# Sheet-BATTERY-V1_0.net
KiCad netlist of a schematic drawn in Altium Designer
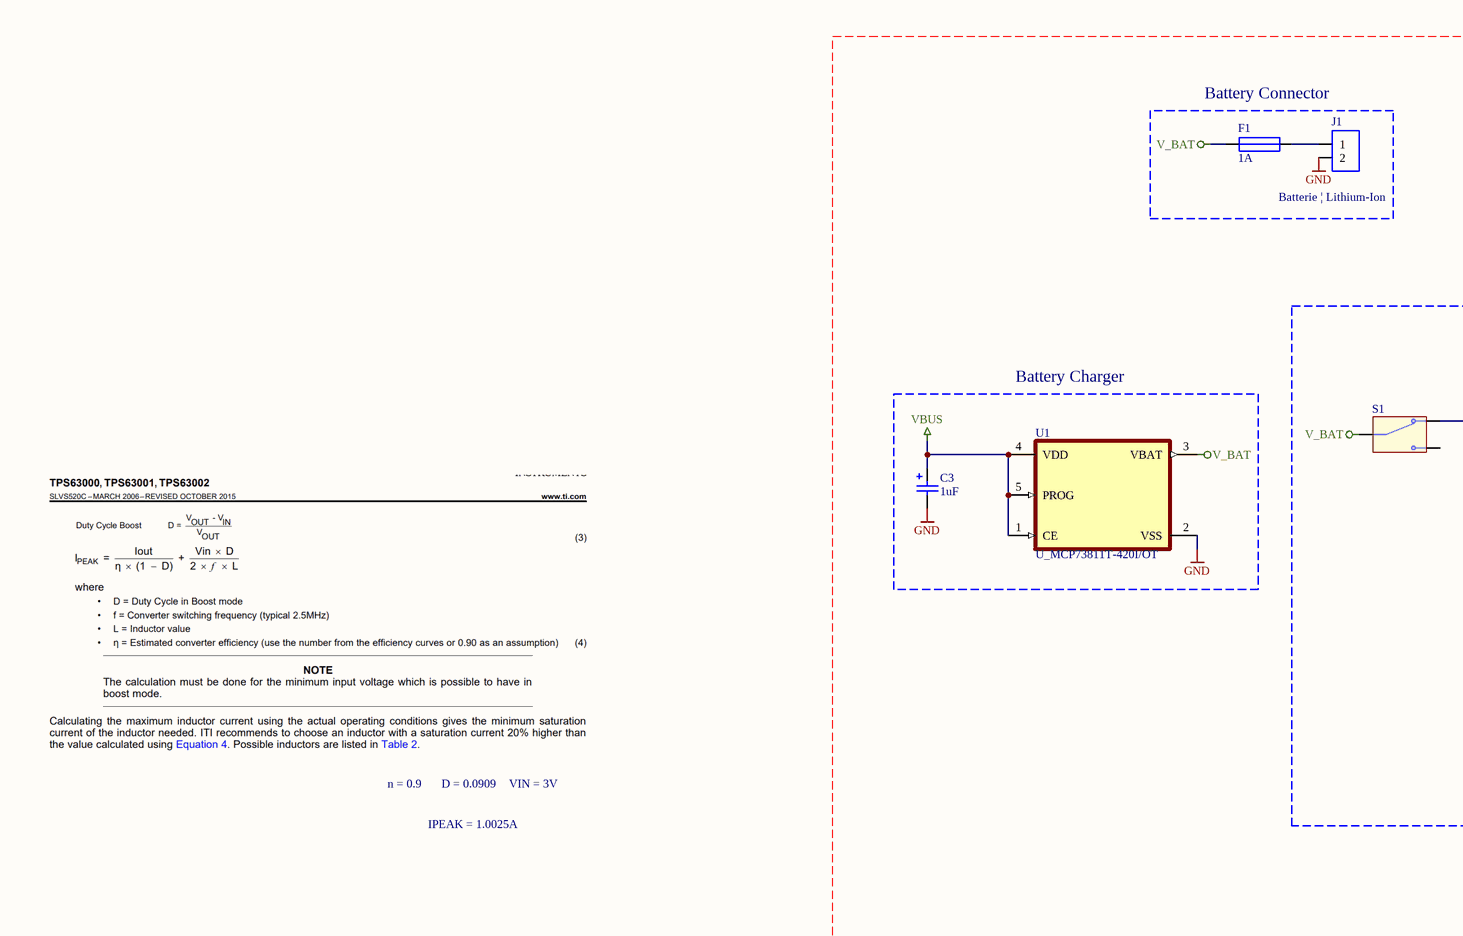
[diagram p0: Sheet-BATTERY-V1.0.SchDoc, left]
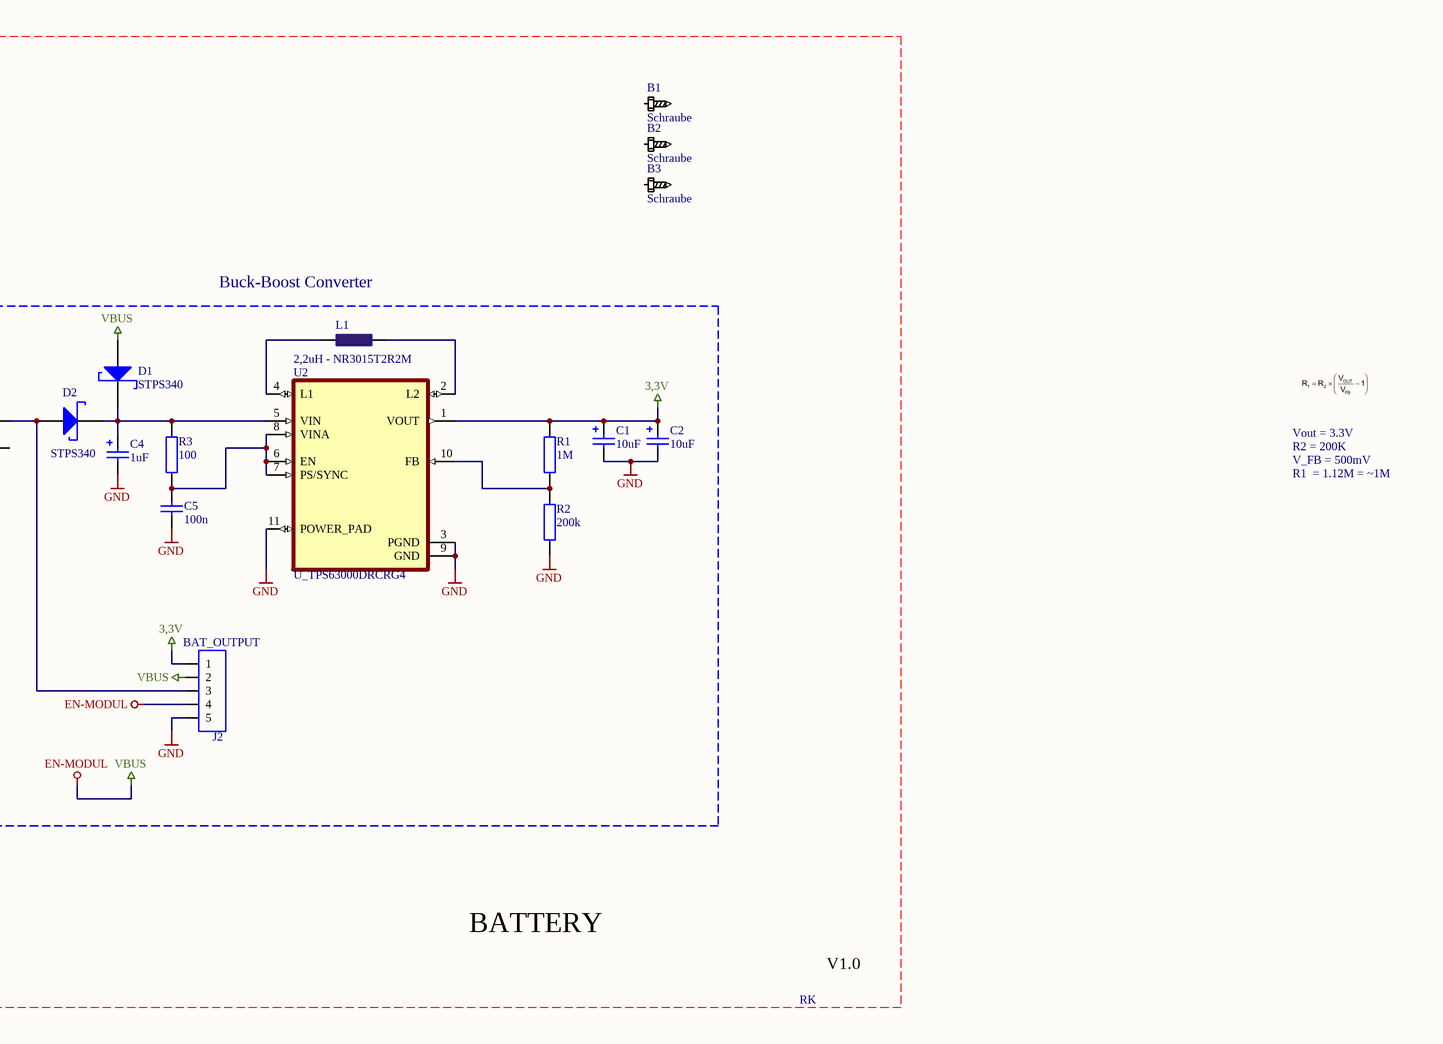
[diagram p1: Sheet-BATTERY-V1.0.SchDoc, right]

(export (version "E")
  (design (tool "Eeschema 10.0.6"))
  (components
    (comp (ref "B1")
      (value "Schraube")
      (footprint "B_Schraube-M3 PAD")
      (description "Schraubenloch für M3 Schrauben")
      (libsource (lib "SCHLIB-PCSB_5.1.3") (part "B_Schraube"))
    )
    (comp (ref "B2")
      (value "Schraube")
      (footprint "B_Schraube-M3 PAD")
      (description "Schraubenloch für M3 Schrauben")
      (libsource (lib "SCHLIB-PCSB_5.1.3") (part "B_Schraube"))
    )
    (comp (ref "B3")
      (value "Schraube")
      (footprint "B_Schraube-M3 PAD")
      (description "Schraubenloch für M3 Schrauben")
      (libsource (lib "SCHLIB-PCSB_5.1.3") (part "B_Schraube"))
    )
    (comp (ref "C1")
      (value "10uF")
      (footprint "C_SMD_B-Typ")
      (description "SMD Elektrolytkondensator")
      (libsource (lib "SCHLIB-PCSB_5.1.3") (part "C_SMD_ELK"))
    )
    (comp (ref "C2")
      (value "10uF")
      (footprint "C_SMD_B-Typ")
      (description "SMD Elektrolytkondensator")
      (libsource (lib "SCHLIB-PCSB_5.1.3") (part "C_SMD_ELK"))
    )
    (comp (ref "C3")
      (value "1uF")
      (footprint "C_SMD_B-Typ")
      (description "SMD Elektrolytkondensator")
      (libsource (lib "SCHLIB-PCSB_5.1.3") (part "C_SMD_ELK"))
    )
    (comp (ref "C4")
      (value "1uF")
      (footprint "C_SMD_B-Typ")
      (description "SMD Elektrolytkondensator")
      (libsource (lib "SCHLIB-PCSB_5.1.3") (part "C_SMD_ELK"))
    )
    (comp (ref "C5")
      (value "100n")
      (footprint "C_SMD_0603")
      (description "Kondensator SMD Universal, Keramik, Folie, usw.")
      (libsource (lib "SCHLIB-PCSB_5.1.3") (part "C_SMD_KO"))
    )
    (comp (ref "D1")
      (value "STPS340")
      (footprint "D_DO-214")
      (description "Diode SMD Schottky")
      (libsource (lib "SCHLIB-PCSB_5.1.3") (part "D_SMD_Schottky"))
    )
    (comp (ref "D2")
      (value "STPS340")
      (footprint "D_DO-214")
      (description "Diode SMD Schottky")
      (libsource (lib "SCHLIB-PCSB_5.1.3") (part "D_SMD_Schottky"))
    )
    (comp (ref "F1")
      (value "1A")
      (footprint "F_OMF63_Schurtner")
      (description "Sicherung")
      (libsource (lib "SCHLIB-PCSB_5.1.3") (part "F_THT_Fuse"))
    )
    (comp (ref "J1")
      (value "Batterie ¦ Lithium-Ion")
      (footprint "J_THT_Printklemme 2x")
      (description "Stecker")
      (libsource (lib "SCHLIB-PCSB_5.1.3") (part "J_THT_CON2"))
    )
    (comp (ref "J2")
      (value "BAT_OUTPUT")
      (footprint "SIP-5")
      (description "Stecker")
      (libsource (lib "SCHLIB-PCSB_5.1.3") (part "J_THT_CON5"))
    )
    (comp (ref "L1")
      (value "2,2uH - NR3015T2R2M")
      (footprint "L_SMD_ND_NR3015T2R2M")
      (description "Spule SMD")
      (libsource (lib "SCHLIB-PCSB_5.1.3") (part "L_SMD_Spule"))
    )
    (comp (ref "R1")
      (value "1M")
      (footprint "R_SMD_0805")
      (description "Widerstand SMD")
      (libsource (lib "SCHLIB-PCSB_5.1.3") (part "R_SMD_Widerstand"))
    )
    (comp (ref "R2")
      (value "200k")
      (footprint "R_SMD_0805")
      (description "Widerstand SMD")
      (libsource (lib "SCHLIB-PCSB_5.1.3") (part "R_SMD_Widerstand"))
    )
    (comp (ref "R3")
      (value "100")
      (footprint "R_SMD_0805")
      (description "Widerstand SMD")
      (libsource (lib "SCHLIB-PCSB_5.1.3") (part "R_SMD_Widerstand"))
    )
    (comp (ref "S1")
      (value "~")
      (footprint "S_THT_SW-3Pol")
      (description "Toggle Switch")
      (fields (field (name "MP") "100SP1T1B4M2QE"))
      (libsource (lib "SCHLIB-PCSB_5.1.3") (part "S_THT_Schalter 3-Pol."))
    )
    (comp (ref "U1")
      (value "U_MCP73811T-420I/OT")
      (footprint "SOT95P280X145-5N")
      (description "Charger IC Lithium Ion/Polymer SOT-23-5")
      (fields (field (name "MF") "Microchip") (field (name "MP") "MCP73811T-420I/OT"))
      (libsource (lib "SCHLIB-PCSB_5.1.3") (part "U_MCP73811T-420I/OT"))
    )
    (comp (ref "U2")
      (value "U_TPS63000DRCRG4")
      (footprint "VREG_V62/16624-01YE")
      (description "High efficiency Buck-Boost Converter with 1.8A Current Switches in 3x3 QFN 10-VSON -40 to 85")
      (fields (field (name "MF") "Texas Instruments") (field (name "MP") "TPS63000DRCRG4"))
      (libsource (lib "SCHLIB-PCSB_5.1.3") (part "U_TPS63000DRCRG4"))
    )
  )
  (nets
    (net (code "1") (name "3,3V") (class "Default")
      (node (ref "C1") (pin "1") (pinfunction "1_1") (pintype "passive"))
      (node (ref "C2") (pin "1") (pinfunction "1_1") (pintype "passive"))
      (node (ref "J2") (pin "1") (pinfunction "1_1") (pintype "passive"))
      (node (ref "R1") (pin "2") (pintype "passive"))
      (node (ref "U2") (pin "1") (pinfunction "VOUT_1") (pintype "output"))
    )
    (net (code "2") (name "EN-MODUL") (class "Default")
      (node (ref "C3") (pin "1") (pinfunction "1_1") (pintype "passive"))
      (node (ref "D1") (pin "1") (pinfunction "A_1") (pintype "passive"))
      (node (ref "J2") (pin "2") (pinfunction "2_2") (pintype "passive"))
      (node (ref "J2") (pin "4") (pinfunction "4_4") (pintype "passive"))
      (node (ref "U1") (pin "1") (pinfunction "CE_1") (pintype "input"))
      (node (ref "U1") (pin "4") (pinfunction "VDD_4") (pintype "power_in"))
      (node (ref "U1") (pin "5") (pinfunction "PROG_5") (pintype "input"))
    )
    (net (code "3") (name "GND") (class "Default")
      (node (ref "C1") (pin "2") (pinfunction "2_2") (pintype "passive"))
      (node (ref "C2") (pin "2") (pinfunction "2_2") (pintype "passive"))
      (node (ref "C3") (pin "2") (pinfunction "2_2") (pintype "passive"))
      (node (ref "C4") (pin "2") (pinfunction "2_2") (pintype "passive"))
      (node (ref "C5") (pin "2") (pintype "passive"))
      (node (ref "J1") (pin "2") (pinfunction "2_2") (pintype "passive"))
      (node (ref "J2") (pin "5") (pinfunction "5_5") (pintype "passive"))
      (node (ref "R2") (pin "1") (pintype "passive"))
      (node (ref "U1") (pin "2") (pinfunction "VSS_2") (pintype "power_in"))
      (node (ref "U2") (pin "11") (pinfunction "POWER_PAD_11") (pintype "bidirectional"))
      (node (ref "U2") (pin "3") (pinfunction "PGND_3") (pintype "power_in"))
      (node (ref "U2") (pin "9") (pinfunction "GND_9") (pintype "power_in"))
    )
    (net (code "4") (name "Net-(D1-K)") (class "Default")
      (node (ref "C4") (pin "1") (pinfunction "1_1") (pintype "passive"))
      (node (ref "D1") (pin "2") (pinfunction "K_2") (pintype "passive"))
      (node (ref "D2") (pin "2") (pinfunction "K_2") (pintype "passive"))
      (node (ref "R3") (pin "2") (pintype "passive"))
      (node (ref "U2") (pin "5") (pinfunction "VIN_5") (pintype "input"))
    )
    (net (code "5") (name "Net-(D2-A)") (class "Default")
      (node (ref "D2") (pin "1") (pinfunction "A_1") (pintype "passive"))
      (node (ref "J2") (pin "3") (pinfunction "3_3") (pintype "passive"))
      (node (ref "S1") (pin "1") (pinfunction "1_1") (pintype "passive"))
    )
    (net (code "6") (name "Net-(F1-Pad2)") (class "Default")
      (node (ref "F1") (pin "2") (pinfunction "2_2") (pintype "passive"))
      (node (ref "J1") (pin "1") (pinfunction "1_1") (pintype "passive"))
    )
    (net (code "7") (name "Net-(U2-EN)") (class "Default")
      (node (ref "C5") (pin "1") (pintype "passive"))
      (node (ref "R3") (pin "1") (pintype "passive"))
      (node (ref "U2") (pin "6") (pinfunction "EN_6") (pintype "input"))
      (node (ref "U2") (pin "7") (pinfunction "PS/SYNC_7") (pintype "input"))
      (node (ref "U2") (pin "8") (pinfunction "VINA_8") (pintype "input"))
    )
    (net (code "8") (name "Net-(U2-FB)") (class "Default")
      (node (ref "R1") (pin "1") (pintype "passive"))
      (node (ref "R2") (pin "2") (pintype "passive"))
      (node (ref "U2") (pin "10") (pinfunction "FB_10") (pintype "input"))
    )
    (net (code "9") (name "Net-(U2-L1)") (class "Default")
      (node (ref "L1") (pin "2") (pintype "passive"))
      (node (ref "U2") (pin "4") (pinfunction "L1_4") (pintype "bidirectional"))
    )
    (net (code "10") (name "Net-(U2-L2)") (class "Default")
      (node (ref "L1") (pin "1") (pintype "passive"))
      (node (ref "U2") (pin "2") (pinfunction "L2_2") (pintype "bidirectional"))
    )
    (net (code "11") (name "V_BAT") (class "Default")
      (node (ref "F1") (pin "1") (pintype "passive"))
      (node (ref "S1") (pin "2") (pinfunction "2_2") (pintype "passive"))
      (node (ref "U1") (pin "3") (pinfunction "VBAT_3") (pintype "output"))
    )
    (net (code "12") (name "unconnected-(B1-PAD-Pad1)") (class "Default")
      (node (ref "B1") (pin "1") (pinfunction "PAD_1") (pintype "passive"))
    )
    (net (code "13") (name "unconnected-(B2-PAD-Pad1)") (class "Default")
      (node (ref "B2") (pin "1") (pinfunction "PAD_1") (pintype "passive"))
    )
    (net (code "14") (name "unconnected-(B3-PAD-Pad1)") (class "Default")
      (node (ref "B3") (pin "1") (pinfunction "PAD_1") (pintype "passive"))
    )
    (net (code "15") (name "unconnected-(S1-Pad3)") (class "Default")
      (node (ref "S1") (pin "3") (pinfunction "3_3") (pintype "passive"))
    )
  )
)
